# VFD_Clock.net
KiCad netlist of a schematic drawn in Altium Designer
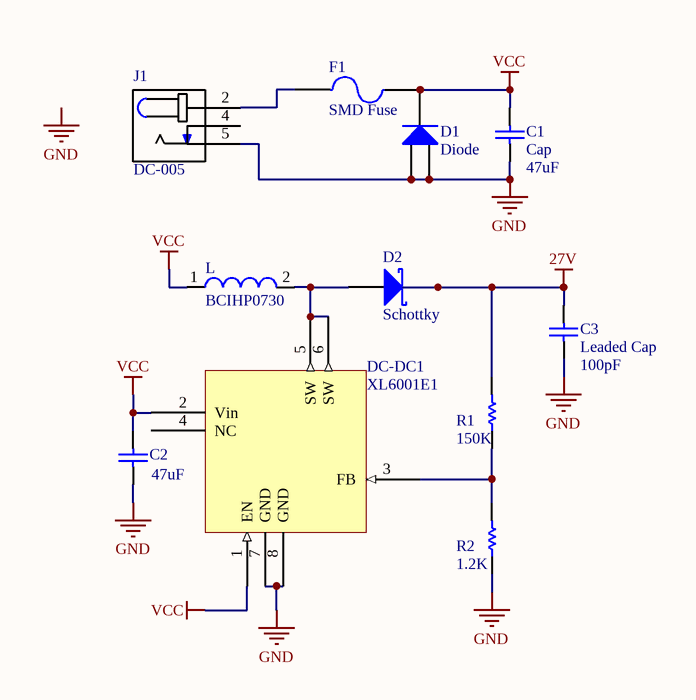
[diagram p0: VFD Clock.SchDoc]

(export (version "E")
  (design (tool "Eeschema 10.0.6"))
  (components
    (comp (ref "C1")
      (value "Cap")
      (footprint "1206")
      (fields (field (name "ALTIUM_VALUE") "47uF") (field (name "PUBLISHER") "Altium Limited"))
      (libsource (lib "XL6001E1") (part "Cap"))
    )
    (comp (ref "C2")
      (value "47uF")
      (footprint "1206")
      (fields (field (name "Comment") "Cap") (field (name "PUBLISHER") "Altium Limited"))
      (libsource (lib "XL6001E1") (part "Cap"))
    )
    (comp (ref "C3")
      (value "Leaded Cap")
      (footprint "RAD-0.1")
      (fields (field (name "ALTIUM_VALUE") "100pF") (field (name "PUBLISHER") "Altium Limited"))
      (libsource (lib "XL6001E1") (part "Leaded Cap"))
    )
    (comp (ref "D1")
      (value "Diode")
      (footprint "PowerDi5")
      (fields (field (name "PUBLISHER") "Altium Limited"))
      (libsource (lib "XL6001E1") (part "Diode"))
    )
    (comp (ref "D2")
      (value "Schottky")
      (footprint "SMB")
      (description "Schottky Diode")
      (fields (field (name "PUBLISHER") "Altium Limited"))
      (libsource (lib "Miscellaneous Devices") (part "D Schottky"))
    )
    (comp (ref "DC-DC1") (value "XL6001E1") (footprint "SOP8") (libsource (lib "XL6001E1") (part "XL6001E1")))
    (comp (ref "F1") (value "SMD Fuse") (footprint "1206") (libsource (lib "XL6001E1") (part "SMD Fuse")))
    (comp (ref "J1")
      (value "DC-005")
      (footprint "NINIGI_DC-005")
      (fields (field (name "MF") "Best Inc."))
      (libsource (lib "XL6001E1") (part "DC-005"))
    )
    (comp (ref "L") (value "BCIHP0730") (footprint "7x7") (libsource (lib "XL6001E1") (part "BCIHP0730")))
    (comp (ref "R1")
      (value "150K")
      (footprint "AXIAL-0.3")
      (description "Resistor")
      (fields (field (name "Comment") "Res1") (field (name "PUBLISHER") "Altium Limited"))
      (libsource (lib "Miscellaneous Devices") (part "Res1"))
    )
    (comp (ref "R2")
      (value "1.2K")
      (footprint "AXIAL-0.3")
      (description "Resistor")
      (fields (field (name "Comment") "Res1") (field (name "PUBLISHER") "Altium Limited"))
      (libsource (lib "Miscellaneous Devices") (part "Res1"))
    )
  )
  (nets
    (net (code "1") (name "27V") (class "Default")
      (node (ref "C3") (pin "2") (pinfunction "2_2") (pintype "passive"))
      (node (ref "D2") (pin "2") (pinfunction "K_2") (pintype "passive"))
      (node (ref "R1") (pin "2") (pinfunction "2_2") (pintype "passive"))
    )
    (net (code "2") (name "GND") (class "Default")
      (node (ref "C1") (pin "1") (pinfunction "1_1") (pintype "passive"))
      (node (ref "C2") (pin "1") (pinfunction "1_1") (pintype "passive"))
      (node (ref "C3") (pin "1") (pinfunction "1_1") (pintype "passive"))
      (node (ref "D1") (pin "1") (pinfunction "A_1") (pintype "passive"))
      (node (ref "D1") (pin "2") (pinfunction "A_2") (pintype "passive"))
      (node (ref "DC-DC1") (pin "7") (pinfunction "GND_7") (pintype "power_in"))
      (node (ref "DC-DC1") (pin "8") (pinfunction "GND_8") (pintype "power_in"))
      (node (ref "J1") (pin "5") (pinfunction "5_5") (pintype "passive"))
      (node (ref "R2") (pin "1") (pinfunction "1_1") (pintype "passive"))
    )
    (net (code "3") (name "Net-(D2-A)") (class "Default")
      (node (ref "D2") (pin "1") (pinfunction "A_1") (pintype "passive"))
      (node (ref "DC-DC1") (pin "5") (pinfunction "SW_5") (pintype "output"))
      (node (ref "DC-DC1") (pin "6") (pinfunction "SW_6") (pintype "output"))
      (node (ref "L") (pin "2") (pinfunction "2_2") (pintype "passive"))
    )
    (net (code "4") (name "Net-(DC-DC1-FB)") (class "Default")
      (node (ref "DC-DC1") (pin "3") (pinfunction "FB_3") (pintype "input"))
      (node (ref "R1") (pin "1") (pinfunction "1_1") (pintype "passive"))
      (node (ref "R2") (pin "2") (pinfunction "2_2") (pintype "passive"))
    )
    (net (code "5") (name "Net-(F1-Pad1)") (class "Default")
      (node (ref "F1") (pin "1") (pinfunction "1_1") (pintype "passive"))
      (node (ref "J1") (pin "2") (pinfunction "2_2") (pintype "passive"))
    )
    (net (code "6") (name "VCC") (class "Default")
      (node (ref "C1") (pin "2") (pinfunction "2_2") (pintype "passive"))
      (node (ref "C2") (pin "2") (pinfunction "2_2") (pintype "passive"))
      (node (ref "D1") (pin "3") (pinfunction "K_3") (pintype "passive"))
      (node (ref "DC-DC1") (pin "1") (pinfunction "EN_1") (pintype "input"))
      (node (ref "DC-DC1") (pin "2") (pinfunction "Vin_2") (pintype "power_in"))
      (node (ref "F1") (pin "2") (pinfunction "2_2") (pintype "passive"))
      (node (ref "L") (pin "1") (pinfunction "1_1") (pintype "passive"))
    )
    (net (code "7") (name "unconnected-(DC-DC1-NC-Pad4)") (class "Default")
      (node (ref "DC-DC1") (pin "4") (pinfunction "NC_4") (pintype "passive"))
    )
    (net (code "8") (name "unconnected-(J1-Pad4)") (class "Default")
      (node (ref "J1") (pin "4") (pinfunction "4_4") (pintype "passive"))
    )
  )
)
